# design.net
KiCad netlist of a schematic drawn in Altium Designer
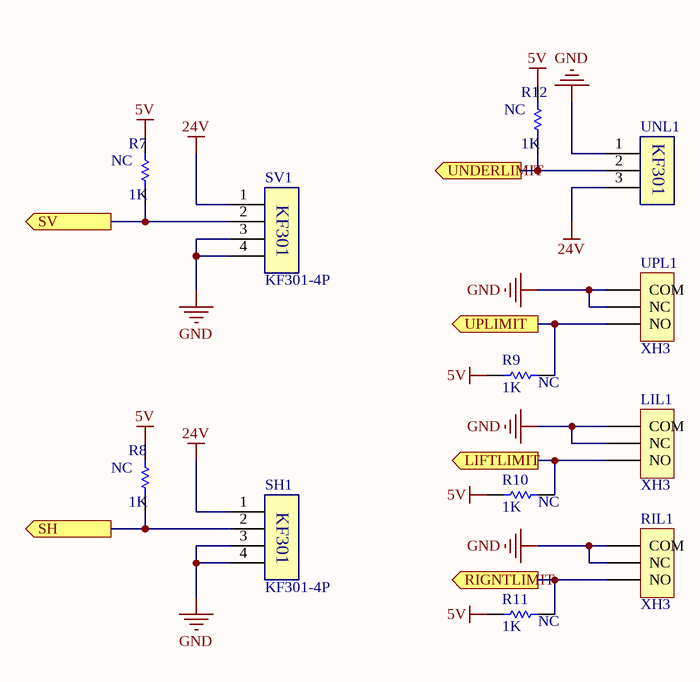
[diagram p0: 反馈模块.SchDoc]

(export (version "E")
  (design (tool "Eeschema 10.0.6"))
  (components
    (comp (ref "LIL1") (value "XH3") (footprint "XH3/2.54mm/180") (libsource (lib "XH，VH") (part "XH3")))
    (comp (ref "R7")
      (value "1K")
      (footprint "0603R")
      (fields (field (name "NOTE") "NC") (field (name "Comment") "RES"))
      (libsource (lib "电阻") (part "RES"))
    )
    (comp (ref "R8")
      (value "1K")
      (footprint "0603R")
      (fields (field (name "NOTE") "NC") (field (name "Comment") "RES"))
      (libsource (lib "电阻") (part "RES"))
    )
    (comp (ref "R9")
      (value "1K")
      (footprint "0603R")
      (fields (field (name "NOTE") "NC") (field (name "Comment") "RES"))
      (libsource (lib "电阻") (part "RES"))
    )
    (comp (ref "R10")
      (value "1K")
      (footprint "0603R")
      (fields (field (name "NOTE") "NC") (field (name "Comment") "RES"))
      (libsource (lib "电阻") (part "RES"))
    )
    (comp (ref "R11")
      (value "1K")
      (footprint "0603R")
      (fields (field (name "NOTE") "NC") (field (name "Comment") "RES"))
      (libsource (lib "电阻") (part "RES"))
    )
    (comp (ref "R12")
      (value "1K")
      (footprint "0603R")
      (fields (field (name "NOTE") "NC") (field (name "Comment") "RES"))
      (libsource (lib "电阻") (part "RES"))
    )
    (comp (ref "RIL1") (value "XH3") (footprint "XH3/2.54mm/180") (libsource (lib "XH，VH") (part "XH3")))
    (comp (ref "SH1")
      (value "KF301-4P")
      (footprint "KF301-5.0-4P")
      (libsource (lib "KF301") (part "KF301-4P"))
    )
    (comp (ref "SV1")
      (value "KF301-4P")
      (footprint "KF301-5.0-4P")
      (libsource (lib "KF301") (part "KF301-4P"))
    )
    (comp (ref "UNL1")
      (value "KF301-3P")
      (footprint "KF301-5.0-3P")
      (libsource (lib "KF301") (part "KF301-3P"))
    )
    (comp (ref "UPL1") (value "XH3") (footprint "XH3/2.54mm/180") (libsource (lib "XH，VH") (part "XH3")))
  )
  (nets
    (net (code "1") (name "/LIFTLIMIT") (class "Default")
      (node (ref "LIL1") (pin "3") (pinfunction "NO_3") (pintype "passive"))
      (node (ref "R10") (pin "1") (pinfunction "1_1") (pintype "passive"))
    )
    (net (code "2") (name "/RIGNTLIMIT") (class "Default")
      (node (ref "R11") (pin "1") (pinfunction "1_1") (pintype "passive"))
      (node (ref "RIL1") (pin "3") (pinfunction "NO_3") (pintype "passive"))
    )
    (net (code "3") (name "/SH") (class "Default")
      (node (ref "R8") (pin "1") (pinfunction "1_1") (pintype "passive"))
      (node (ref "SH1") (pin "2") (pinfunction "2_2") (pintype "passive"))
    )
    (net (code "4") (name "/SV") (class "Default")
      (node (ref "R7") (pin "1") (pinfunction "1_1") (pintype "passive"))
      (node (ref "SV1") (pin "2") (pinfunction "2_2") (pintype "passive"))
    )
    (net (code "5") (name "/UNDERLIMIT") (class "Default")
      (node (ref "R12") (pin "1") (pinfunction "1_1") (pintype "passive"))
      (node (ref "UNL1") (pin "2") (pinfunction "VIN_2") (pintype "passive"))
    )
    (net (code "6") (name "/UPLIMIT") (class "Default")
      (node (ref "R9") (pin "1") (pinfunction "1_1") (pintype "passive"))
      (node (ref "UPL1") (pin "3") (pinfunction "NO_3") (pintype "passive"))
    )
    (net (code "7") (name "5V") (class "Default")
      (node (ref "R10") (pin "2") (pinfunction "2_2") (pintype "passive"))
      (node (ref "R11") (pin "2") (pinfunction "2_2") (pintype "passive"))
      (node (ref "R12") (pin "2") (pinfunction "2_2") (pintype "passive"))
      (node (ref "R7") (pin "2") (pinfunction "2_2") (pintype "passive"))
      (node (ref "R8") (pin "2") (pinfunction "2_2") (pintype "passive"))
      (node (ref "R9") (pin "2") (pinfunction "2_2") (pintype "passive"))
    )
    (net (code "8") (name "24V") (class "Default")
      (node (ref "SH1") (pin "1") (pinfunction "1_1") (pintype "passive"))
      (node (ref "SV1") (pin "1") (pinfunction "1_1") (pintype "passive"))
      (node (ref "UNL1") (pin "3") (pinfunction "VCC_3") (pintype "passive"))
    )
    (net (code "9") (name "GND") (class "Default")
      (node (ref "LIL1") (pin "1") (pinfunction "COM_1") (pintype "passive"))
      (node (ref "LIL1") (pin "2") (pinfunction "NC_2") (pintype "passive"))
      (node (ref "RIL1") (pin "1") (pinfunction "COM_1") (pintype "passive"))
      (node (ref "RIL1") (pin "2") (pinfunction "NC_2") (pintype "passive"))
      (node (ref "SH1") (pin "3") (pinfunction "3_3") (pintype "passive"))
      (node (ref "SH1") (pin "4") (pinfunction "4_4") (pintype "passive"))
      (node (ref "SV1") (pin "3") (pinfunction "3_3") (pintype "passive"))
      (node (ref "SV1") (pin "4") (pinfunction "4_4") (pintype "passive"))
      (node (ref "UNL1") (pin "1") (pinfunction "GND_1") (pintype "passive"))
      (node (ref "UPL1") (pin "1") (pinfunction "COM_1") (pintype "passive"))
      (node (ref "UPL1") (pin "2") (pinfunction "NC_2") (pintype "passive"))
    )
  )
)
